# 06-STM32WL3-RX.net
KiCad netlist of a schematic drawn in Altium Designer
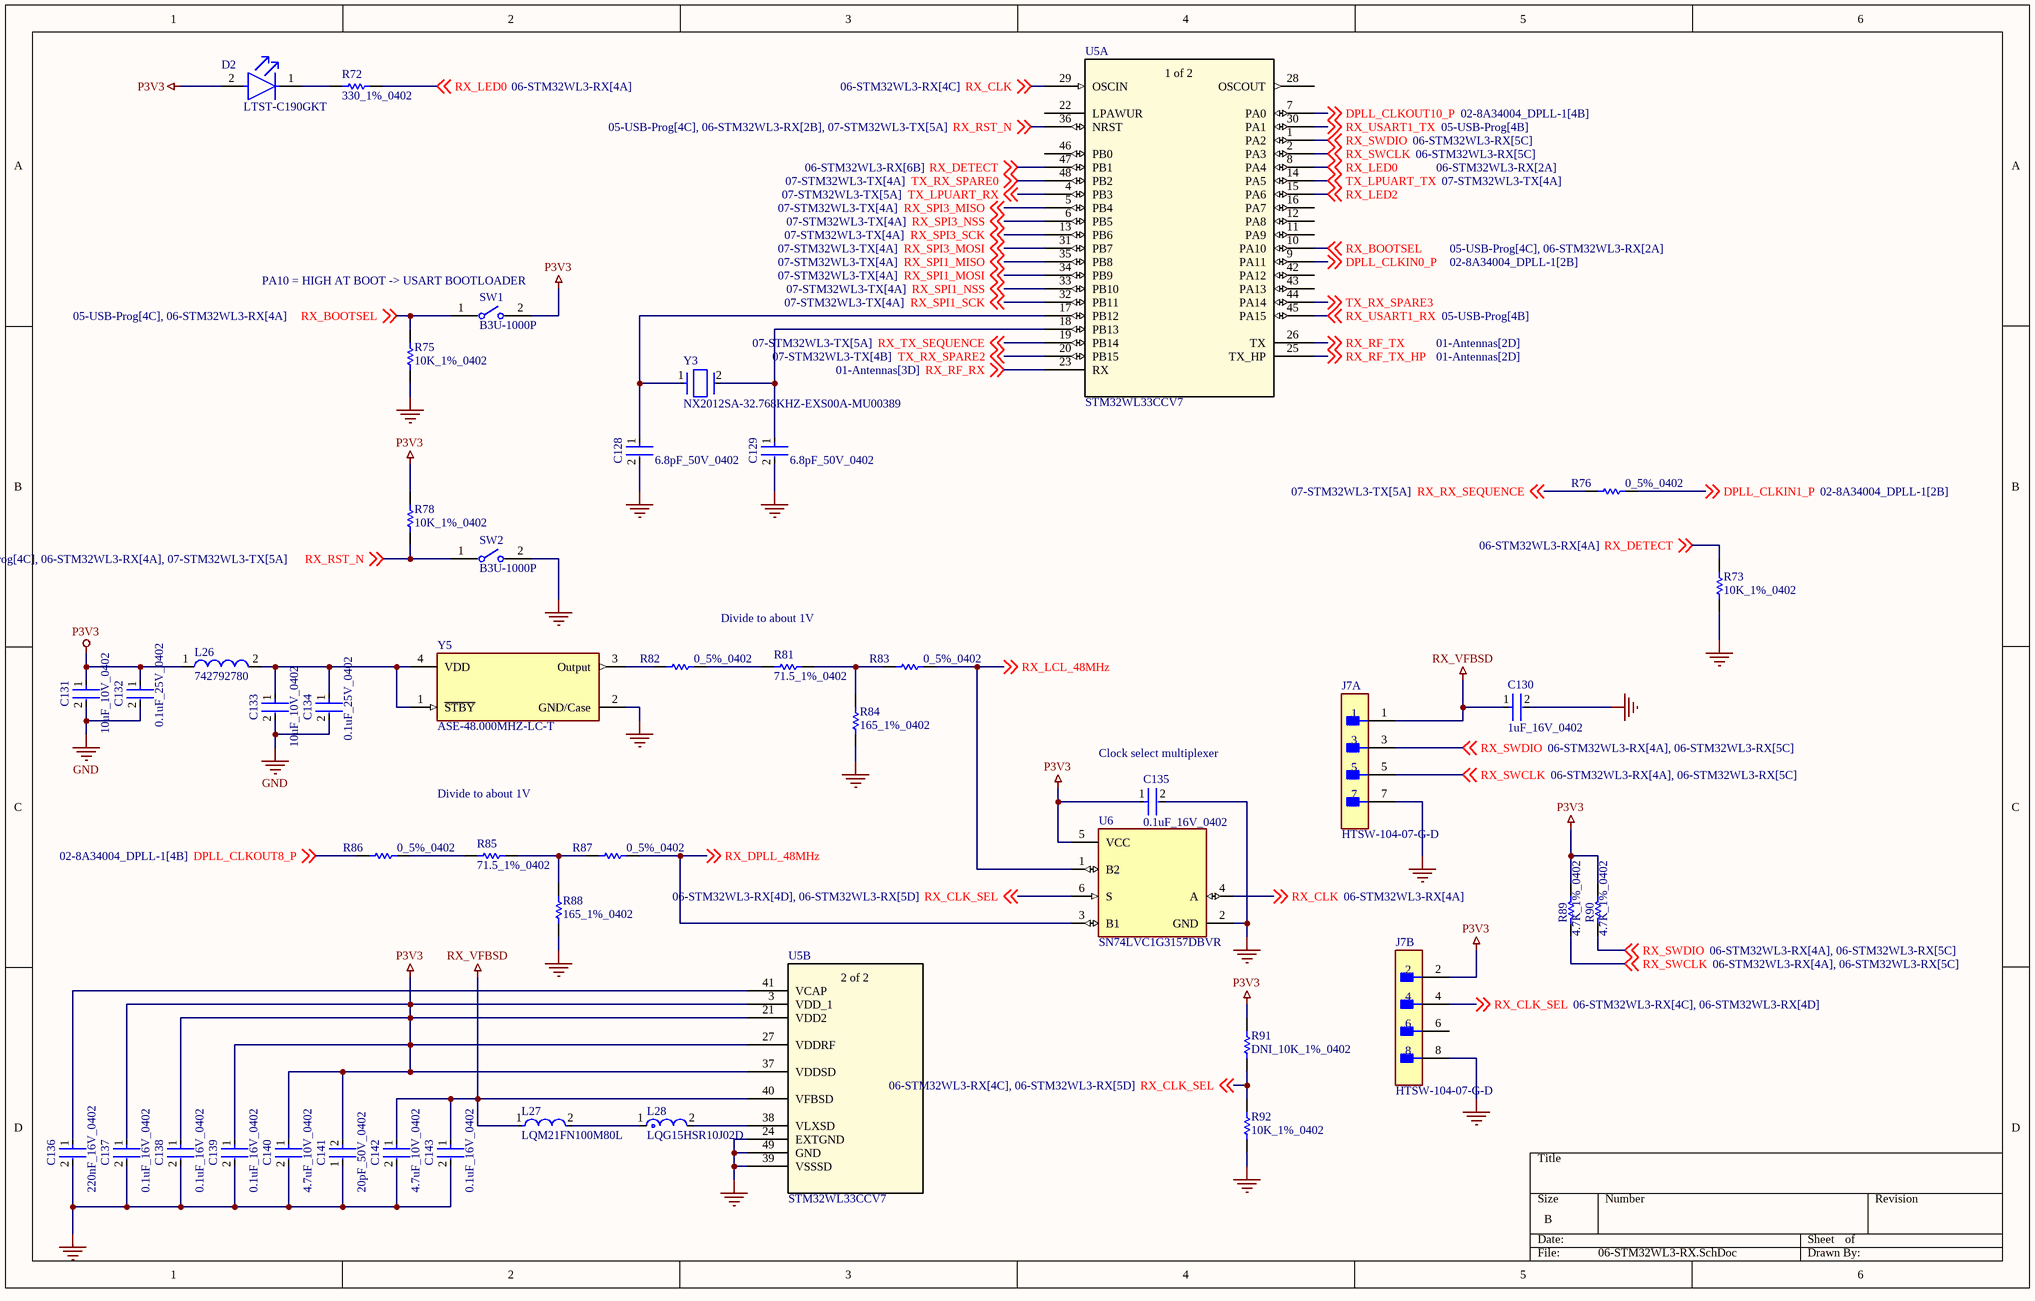
[diagram p0: 06-STM32WL3-RX.SchDoc]

(export (version "E")
  (design (tool "Eeschema 10.0.6"))
  (components
    (comp (ref "C128")
      (value "6.8pF_50V_0402")
      (footprint "FP-GJM155-0_05-IPC_A")
      (description "Multi-Layer Ceramic Capacitor 6.8pF C0G  ±0.25pF 0402 Paper T/R")
      (fields (field (name "VOLTAGE") "50V"))
      (libsource (lib "Altium Content Vault") (part "02cd4be3c70576c341d710602a673aa"))
    )
    (comp (ref "C129")
      (value "6.8pF_50V_0402")
      (footprint "FP-GJM155-0_05-IPC_A")
      (description "Multi-Layer Ceramic Capacitor 6.8pF C0G  ±0.25pF 0402 Paper T/R")
      (fields (field (name "VOLTAGE") "50V"))
      (libsource (lib "Altium Content Vault") (part "02cd4be3c70576c341d710602a673aa"))
    )
    (comp (ref "C130")
      (value "1uF_16V_0402")
      (footprint "FP-0402-L_1_0_0_05-W_0_5-IPC_A")
      (description "None")
      (fields (field (name "TOLERANCE") "10%"))
      (libsource (lib "Altium Content Vault") (part "b4654b650e69147ec39a6b967a45e02"))
    )
    (comp (ref "C131")
      (value "10uF_10V_0402")
      (footprint "FP-CL05A106MP5NUNC-MFG")
      (description "CAP CER 10UF 10V X5R 0402")
      (fields
        (field (name "OCTOPART") "https://octopart.com/cl05a106mp5nunc-samsung-22457395")
        (field (name "TOLERANCE") "20%")
      )
      (libsource (lib "Altium Content Vault") (part "b4654b650e69147ec39a6b967a45e02"))
    )
    (comp (ref "C132")
      (value "0.1uF_25V_0402")
      (footprint "FP-0402-L_1_0_1-W_0_5_0_1-IPC_C")
      (description "General Purpose Ceramic Capacitor, 0402, 100nF, 10%, X7R, 15%, 25V")
      (fields (field (name "VOLTAGE") "25V") (field (name "TOLERANCE") "10%"))
      (libsource (lib "Altium Content Vault") (part "b4654b650e69147ec39a6b967a45e02"))
    )
    (comp (ref "C133")
      (value "10uF_10V_0402")
      (footprint "FP-CL05A106MP5NUNC-MFG")
      (description "CAP CER 10UF 10V X5R 0402")
      (fields
        (field (name "OCTOPART") "https://octopart.com/cl05a106mp5nunc-samsung-22457395")
        (field (name "TOLERANCE") "20%")
      )
      (libsource (lib "Altium Content Vault") (part "b4654b650e69147ec39a6b967a45e02"))
    )
    (comp (ref "C134")
      (value "0.1uF_25V_0402")
      (footprint "FP-0402-L_1_0_1-W_0_5_0_1-IPC_C")
      (description "General Purpose Ceramic Capacitor, 0402, 100nF, 10%, X7R, 15%, 25V")
      (fields (field (name "VOLTAGE") "25V") (field (name "TOLERANCE") "10%"))
      (libsource (lib "Altium Content Vault") (part "b4654b650e69147ec39a6b967a45e02"))
    )
    (comp (ref "C135")
      (value "0.1uF_16V_0402")
      (footprint "FP-C0402-BB-MFG")
      (description "CAP CER 0.1UF 16V 5% X7R 0402")
      (fields
        (field (name "MANUFACTURER") "Kemet")
        (field (name "MANUFACTURER PART NUMBER") "C0402C104J4RACTU")
      )
      (libsource (lib "Altium Content Vault") (part "b4654b650e69147ec39a6b967a45e02"))
    )
    (comp (ref "C136")
      (value "220nF_16V_0402")
      (footprint "FP-GRM155-0_05-IPC_C")
      (description "Chip Multilayer Ceramic Capacitors for General Purpose, 0402, 0.22uF, X7R, 15%, 10%, 16V")
      (fields (field (name "VOLTAGE") "16V") (field (name "TOLERANCE") "10%"))
      (libsource (lib "Altium Content Vault") (part "02cd4be3c70576c341d710602a673aa"))
    )
    (comp (ref "C137")
      (value "0.1uF_16V_0402")
      (footprint "FP-C0402-BB-MFG")
      (description "CAP CER 0.1UF 16V 5% X7R 0402")
      (fields
        (field (name "MANUFACTURER") "Kemet")
        (field (name "MANUFACTURER PART NUMBER") "C0402C104J4RACTU")
      )
      (libsource (lib "Altium Content Vault") (part "b4654b650e69147ec39a6b967a45e02"))
    )
    (comp (ref "C138")
      (value "0.1uF_16V_0402")
      (footprint "FP-C0402-BB-MFG")
      (description "CAP CER 0.1UF 16V 5% X7R 0402")
      (fields
        (field (name "MANUFACTURER") "Kemet")
        (field (name "MANUFACTURER PART NUMBER") "C0402C104J4RACTU")
      )
      (libsource (lib "Altium Content Vault") (part "b4654b650e69147ec39a6b967a45e02"))
    )
    (comp (ref "C139")
      (value "0.1uF_16V_0402")
      (footprint "FP-C0402-BB-MFG")
      (description "CAP CER 0.1UF 16V 5% X7R 0402")
      (fields
        (field (name "MANUFACTURER") "Kemet")
        (field (name "MANUFACTURER PART NUMBER") "C0402C104J4RACTU")
      )
      (libsource (lib "Altium Content Vault") (part "b4654b650e69147ec39a6b967a45e02"))
    )
    (comp (ref "C140")
      (value "4.7uF_10V_0402")
      (footprint "FP-C1005-050-0_15-MFG")
      (description "CAP CER 4.7UF 10V X5R 0402")
      (fields (field (name "TOLERANCE") "10%"))
      (libsource (lib "Altium Content Vault") (part "b4654b650e69147ec39a6b967a45e02"))
    )
    (comp (ref "C141")
      (value "20pF_50V_0402")
      (footprint "FP-CBR04C-MFG")
      (description "CAP CER 20PF 50V C0G/NP0 0402")
      (fields
        (field (name "MANUFACTURER") "KEMET")
        (field (name "OCTOPART") "https://octopart.com/cbr04c200j5gac-kemet-20446742")
      )
      (libsource (lib "Altium Content Vault") (part "236180d848d6139a670b325ea6854c9"))
    )
    (comp (ref "C142")
      (value "4.7uF_10V_0402")
      (footprint "FP-C1005-050-0_15-MFG")
      (description "CAP CER 4.7UF 10V X5R 0402")
      (fields (field (name "TOLERANCE") "10%"))
      (libsource (lib "Altium Content Vault") (part "b4654b650e69147ec39a6b967a45e02"))
    )
    (comp (ref "C143")
      (value "0.1uF_16V_0402")
      (footprint "FP-C0402-BB-MFG")
      (description "CAP CER 0.1UF 16V 5% X7R 0402")
      (fields
        (field (name "MANUFACTURER") "Kemet")
        (field (name "MANUFACTURER PART NUMBER") "C0402C104J4RACTU")
      )
      (libsource (lib "Altium Content Vault") (part "b4654b650e69147ec39a6b967a45e02"))
    )
    (comp (ref "D2")
      (value "LTST-C190GKT")
      (footprint "FP-LTST-C190GKT-MFG")
      (description "LED GREEN CLEAR CHIP SMD")
      (fields (field (name "VOLTAGE") "2V"))
      (libsource (lib "Altium Content Vault") (part "8706943c75ba83719d021d2fdc84c58"))
    )
    (comp (ref "J7")
      (value "HTSW-104-07-G-D")
      (footprint "FP-HTSW-104-07-G-D-MFG")
      (description "CONN HEADER VERT 8POS 2.54MM")
      (fields
        (field (name "MANUFACTURER") "Samtec")
        (field (name "OCTOPART") "https://octopart.com/htsw-104-07-g-d-samtec-10613822")
      )
      (libsource (lib "Altium Content Vault") (part "811e954b9c034aa737de4d9295cbe7e"))
    )
    (comp (ref "L26")
      (value "742792780")
      (footprint "SMD-0402")
      (description "SMD EMI Suppression Ferrite Bead WE-CBF, Z = 220 Ohm")
      (libsource (lib "Altium Content Vault") (part "PAS-IND-INDUCTOR-2"))
    )
    (comp (ref "L27")
      (value "LQM21FN100M80L")
      (footprint "FP-LQM21DH_70-IPC_C")
      (description "Multilayer Type Inductor for Power Lines, 0805 (2012), 10μH, 20%, 0.39Ω, 100mA")
      (fields (field (name "TOLERANCE") "20%"))
      (libsource (lib "Altium Content Vault") (part "725321dda6339637d4d059423bc1c3c"))
    )
    (comp (ref "L28")
      (value "LQG15HSR10J02D")
      (footprint "FP-LQG15HH_02-IPC_A")
      (description "Multilayer type RF Inductor 100nH ±5% 1.25Ω 200mA 0402")
      (fields (field (name "TOLERANCE") "5%"))
      (libsource (lib "Altium Content Vault") (part "4cc4b267dca4c8e51f7102f422741d8"))
    )
    (comp (ref "R72")
      (value "330_1%_0402")
      (footprint "RESC1005X40X25NL10T10")
      (fields (field (name "MANUFACTURER") "Panasonic") (field (name "PART NUMBER") "ERA-2AED331X"))
      (libsource (lib "Altium Content Vault") (part "RES"))
    )
    (comp (ref "R73")
      (value "10K_1%_0402")
      (footprint "RESC1005X40X25NL10T10")
      (fields (field (name "MANUFACTURER") "Bourns") (field (name "PART NUMBER") "CR0402-FX-1002GLF"))
      (libsource (lib "Altium Content Vault") (part "RES"))
    )
    (comp (ref "R75")
      (value "10K_1%_0402")
      (footprint "RESC1005X40X25NL10T10")
      (fields (field (name "MANUFACTURER") "Bourns") (field (name "PART NUMBER") "CR0402-FX-1002GLF"))
      (libsource (lib "Altium Content Vault") (part "RES"))
    )
    (comp (ref "R76")
      (value "0_5%_0402")
      (footprint "RESC1005X40X25NL05T10")
      (fields (field (name "MANUFACTURER") "Panasonic") (field (name "PART NUMBER") "ERJ-U020R00X"))
      (libsource (lib "Altium Content Vault") (part "RES"))
    )
    (comp (ref "R78")
      (value "10K_1%_0402")
      (footprint "RESC1005X40X25NL10T10")
      (fields (field (name "MANUFACTURER") "Bourns") (field (name "PART NUMBER") "CR0402-FX-1002GLF"))
      (libsource (lib "Altium Content Vault") (part "RES"))
    )
    (comp (ref "R81")
      (value "71.5_1%_0402")
      (footprint "RESC1005X40X25NL05T05")
      (fields (field (name "MANUFACTURER") "Vishay Dale") (field (name "PART NUMBER") "CRCW040271R5FKED"))
      (libsource (lib "Altium Content Vault") (part "RES"))
    )
    (comp (ref "R82")
      (value "0_5%_0402")
      (footprint "RESC1005X40X25NL05T10")
      (fields (field (name "MANUFACTURER") "Panasonic") (field (name "PART NUMBER") "ERJ-U020R00X"))
      (libsource (lib "Altium Content Vault") (part "RES"))
    )
    (comp (ref "R83")
      (value "0_5%_0402")
      (footprint "RESC1005X40X25NL05T10")
      (fields (field (name "MANUFACTURER") "Panasonic") (field (name "PART NUMBER") "ERJ-U020R00X"))
      (libsource (lib "Altium Content Vault") (part "RES"))
    )
    (comp (ref "R84")
      (value "165_1%_0402")
      (footprint "RESC1005X40X25NL05T05")
      (fields (field (name "MANUFACTURER") "Vishay Dale") (field (name "PART NUMBER") "CRCW0402165RFKED"))
      (libsource (lib "Altium Content Vault") (part "RES"))
    )
    (comp (ref "R85")
      (value "71.5_1%_0402")
      (footprint "RESC1005X40X25NL05T05")
      (fields (field (name "MANUFACTURER") "Vishay Dale") (field (name "PART NUMBER") "CRCW040271R5FKED"))
      (libsource (lib "Altium Content Vault") (part "RES"))
    )
    (comp (ref "R86")
      (value "0_5%_0402")
      (footprint "RESC1005X40X25NL05T10")
      (fields (field (name "MANUFACTURER") "Panasonic") (field (name "PART NUMBER") "ERJ-U020R00X"))
      (libsource (lib "Altium Content Vault") (part "RES"))
    )
    (comp (ref "R87")
      (value "0_5%_0402")
      (footprint "RESC1005X40X25NL05T10")
      (fields (field (name "MANUFACTURER") "Panasonic") (field (name "PART NUMBER") "ERJ-U020R00X"))
      (libsource (lib "Altium Content Vault") (part "RES"))
    )
    (comp (ref "R88")
      (value "165_1%_0402")
      (footprint "RESC1005X40X25NL05T05")
      (fields (field (name "MANUFACTURER") "Vishay Dale") (field (name "PART NUMBER") "CRCW0402165RFKED"))
      (libsource (lib "Altium Content Vault") (part "RES"))
    )
    (comp (ref "R89")
      (value "4.7K_1%_0402")
      (footprint "RESC1005X40X25NL10T10")
      (fields (field (name "MANUFACTURER") "Bourns") (field (name "PART NUMBER") "CR0402-FX-4701GLF"))
      (libsource (lib "Altium Content Vault") (part "RES"))
    )
    (comp (ref "R90")
      (value "4.7K_1%_0402")
      (footprint "RESC1005X40X25NL10T10")
      (fields (field (name "MANUFACTURER") "Bourns") (field (name "PART NUMBER") "CR0402-FX-4701GLF"))
      (libsource (lib "Altium Content Vault") (part "RES"))
    )
    (comp (ref "R91")
      (value "DNI_10K_1%_0402")
      (footprint "RESC1005X40X25NL10T10")
      (fields (field (name "MANUFACTURER") "Bourns") (field (name "PART NUMBER") "CR0402-FX-1002GLF"))
      (libsource (lib "Altium Content Vault") (part "RES"))
    )
    (comp (ref "R92")
      (value "10K_1%_0402")
      (footprint "RESC1005X40X25NL10T10")
      (fields (field (name "MANUFACTURER") "Bourns") (field (name "PART NUMBER") "CR0402-FX-1002GLF"))
      (libsource (lib "Altium Content Vault") (part "RES"))
    )
    (comp (ref "SW1")
      (value "B3U-1000P")
      (footprint "FP-B3U-1000P-MFG")
      (description "SWITCH TACTILE SPST-NO 0.05A 12V")
      (libsource (lib "Altium Content Vault") (part "ae622034201233ca1abcedc05908f33"))
    )
    (comp (ref "SW2")
      (value "B3U-1000P")
      (footprint "FP-B3U-1000P-MFG")
      (description "SWITCH TACTILE SPST-NO 0.05A 12V")
      (libsource (lib "Altium Content Vault") (part "ae622034201233ca1abcedc05908f33"))
    )
    (comp (ref "U5")
      (value "STM32WL33CCV7")
      (footprint "UFQFPN-48_STM")
      (description "No Description Available")
      (libsource (lib "STM32WL33CCV7") (part "STM32WL33CCV7"))
    )
    (comp (ref "U6")
      (value "SN74LVC1G3157DBVR")
      (footprint "FP-DBV0006A-IPC_C")
      (description "IC SWITCH SPDT SOT23-6")
      (libsource (lib "Altium Content Vault") (part "14cfcf06f1431fbc89496e2a44d6624"))
    )
    (comp (ref "Y3")
      (value "NX2012SA-32.768KHZ-EXS00A-MU00389")
      (footprint "FP-NX2012SA-MFG")
      (description "CRYSTAL 32.768KHZ 7PF SMD")
      (fields
        (field (name "MANUFACTURER") "NDK America")
        (field (name "OCTOPART") "https://octopart.com/nx2012sa-32.768khz-exs00a-mu00389-ndk-92010294")
      )
      (libsource (lib "Altium Content Vault") (part "c23a69dc6c9e2f18f2079038eb95dd1"))
    )
    (comp (ref "Y5")
      (value "ASE-48.000MHZ-LC-T")
      (footprint "FP-ASE-MFG")
      (description "XTAL Oscillator 48MHz ±50ppm CMOS 3.3V 4-SMD 3.2mm x 2.5mm")
      (libsource (lib "Altium Content Vault") (part "61a724e6190563596ac712fef61ad37"))
    )
  )
  (nets
    (net (code "1") (name "DPLL_CLKIN0_P") (class "Default")
      (node (ref "U5") (pin "9") (pinfunction "PA11_9") (pintype "bidirectional"))
    )
    (net (code "2") (name "DPLL_CLKIN1_P") (class "Default")
      (node (ref "R76") (pin "2") (pinfunction "2_2") (pintype "passive"))
    )
    (net (code "3") (name "DPLL_CLKOUT8_P") (class "Default")
      (node (ref "R86") (pin "1") (pinfunction "1_1") (pintype "passive"))
    )
    (net (code "4") (name "DPLL_CLKOUT10_P") (class "Default")
      (node (ref "U5") (pin "7") (pinfunction "PA0_7") (pintype "bidirectional"))
    )
    (net (code "5") (name "GND") (class "Default")
      (node (ref "C128") (pin "2") (pinfunction "2_2") (pintype "passive"))
      (node (ref "C129") (pin "2") (pinfunction "2_2") (pintype "passive"))
      (node (ref "C130") (pin "2") (pinfunction "2_2") (pintype "passive"))
      (node (ref "C131") (pin "2") (pinfunction "2_2") (pintype "passive"))
      (node (ref "C132") (pin "2") (pinfunction "2_2") (pintype "passive"))
      (node (ref "C133") (pin "2") (pinfunction "2_2") (pintype "passive"))
      (node (ref "C134") (pin "2") (pinfunction "2_2") (pintype "passive"))
      (node (ref "C135") (pin "2") (pinfunction "2_2") (pintype "passive"))
      (node (ref "C136") (pin "2") (pinfunction "2_2") (pintype "passive"))
      (node (ref "C137") (pin "2") (pinfunction "2_2") (pintype "passive"))
      (node (ref "C138") (pin "2") (pinfunction "2_2") (pintype "passive"))
      (node (ref "C139") (pin "2") (pinfunction "2_2") (pintype "passive"))
      (node (ref "C140") (pin "2") (pinfunction "2_2") (pintype "passive"))
      (node (ref "C141") (pin "1") (pinfunction "1_1") (pintype "passive"))
      (node (ref "C142") (pin "2") (pinfunction "2_2") (pintype "passive"))
      (node (ref "C143") (pin "2") (pinfunction "2_2") (pintype "passive"))
      (node (ref "J7") (pin "7") (pinfunction "7_7") (pintype "passive"))
      (node (ref "J7") (pin "8") (pinfunction "8_8") (pintype "passive"))
      (node (ref "R73") (pin "2") (pinfunction "2_2") (pintype "passive"))
      (node (ref "R75") (pin "2") (pinfunction "2_2") (pintype "passive"))
      (node (ref "R84") (pin "1") (pinfunction "1_1") (pintype "passive"))
      (node (ref "R88") (pin "1") (pinfunction "1_1") (pintype "passive"))
      (node (ref "R92") (pin "2") (pinfunction "2_2") (pintype "passive"))
      (node (ref "SW2") (pin "2") (pinfunction "2_2") (pintype "passive"))
      (node (ref "U5") (pin "24") (pinfunction "EXTGND_24") (pintype "power_in"))
      (node (ref "U5") (pin "39") (pinfunction "VSSSD_39") (pintype "power_in"))
      (node (ref "U5") (pin "49") (pinfunction "GND_49") (pintype "power_in"))
      (node (ref "U6") (pin "2") (pinfunction "GND_2") (pintype "power_in"))
      (node (ref "Y5") (pin "2") (pinfunction "GND/Case_2") (pintype "power_in"))
    )
    (net (code "6") (name "Net-(D2-C)") (class "Default")
      (node (ref "D2") (pin "1") (pinfunction "C_1") (pintype "passive"))
      (node (ref "R72") (pin "2") (pinfunction "2_2") (pintype "passive"))
    )
    (net (code "7") (name "Net-(L27-Pad2)") (class "Default")
      (node (ref "L27") (pin "2") (pinfunction "2_2") (pintype "passive"))
      (node (ref "L28") (pin "1") (pinfunction "1_1") (pintype "passive"))
    )
    (net (code "8") (name "Net-(R81-Pad1)") (class "Default")
      (node (ref "R81") (pin "1") (pinfunction "1_1") (pintype "passive"))
      (node (ref "R82") (pin "2") (pinfunction "2_2") (pintype "passive"))
    )
    (net (code "9") (name "Net-(R81-Pad2)") (class "Default")
      (node (ref "R81") (pin "2") (pinfunction "2_2") (pintype "passive"))
      (node (ref "R83") (pin "1") (pinfunction "1_1") (pintype "passive"))
      (node (ref "R84") (pin "2") (pinfunction "2_2") (pintype "passive"))
    )
    (net (code "10") (name "Net-(R85-Pad1)") (class "Default")
      (node (ref "R85") (pin "1") (pinfunction "1_1") (pintype "passive"))
      (node (ref "R86") (pin "2") (pinfunction "2_2") (pintype "passive"))
    )
    (net (code "11") (name "Net-(R85-Pad2)") (class "Default")
      (node (ref "R85") (pin "2") (pinfunction "2_2") (pintype "passive"))
      (node (ref "R87") (pin "1") (pinfunction "1_1") (pintype "passive"))
      (node (ref "R88") (pin "2") (pinfunction "2_2") (pintype "passive"))
    )
    (net (code "12") (name "Net-(U5A-PB12)") (class "Default")
      (node (ref "C128") (pin "1") (pinfunction "1_1") (pintype "passive"))
      (node (ref "U5") (pin "17") (pinfunction "PB12_17") (pintype "bidirectional"))
      (node (ref "Y3") (pin "1") (pinfunction "1_1") (pintype "passive"))
    )
    (net (code "13") (name "Net-(U5A-PB13)") (class "Default")
      (node (ref "C129") (pin "1") (pinfunction "1_1") (pintype "passive"))
      (node (ref "U5") (pin "18") (pinfunction "PB13_18") (pintype "bidirectional"))
      (node (ref "Y3") (pin "2") (pinfunction "2_2") (pintype "passive"))
    )
    (net (code "14") (name "Net-(U5B-VCAP)") (class "Default")
      (node (ref "C136") (pin "1") (pinfunction "1_1") (pintype "passive"))
      (node (ref "U5") (pin "41") (pinfunction "VCAP_41") (pintype "power_in"))
    )
    (net (code "15") (name "Net-(U5B-VLXSD)") (class "Default")
      (node (ref "L28") (pin "2") (pinfunction "2_2") (pintype "passive"))
      (node (ref "U5") (pin "38") (pinfunction "VLXSD_38") (pintype "power_in"))
    )
    (net (code "16") (name "Net-(Y5-Output)") (class "Default")
      (node (ref "R82") (pin "1") (pinfunction "1_1") (pintype "passive"))
      (node (ref "Y5") (pin "3") (pinfunction "Output_3") (pintype "output"))
    )
    (net (code "17") (name "Net-(Y5-VDD)") (class "Default")
      (node (ref "C133") (pin "1") (pinfunction "1_1") (pintype "passive"))
      (node (ref "C134") (pin "1") (pinfunction "1_1") (pintype "passive"))
      (node (ref "L26") (pin "2") (pinfunction "2_2") (pintype "passive"))
      (node (ref "Y5") (pin "1") (pinfunction "~{STBY}_1") (pintype "input"))
      (node (ref "Y5") (pin "4") (pinfunction "VDD_4") (pintype "power_in"))
    )
    (net (code "18") (name "P3V3") (class "Default")
      (node (ref "C131") (pin "1") (pinfunction "1_1") (pintype "passive"))
      (node (ref "C132") (pin "1") (pinfunction "1_1") (pintype "passive"))
      (node (ref "C135") (pin "1") (pinfunction "1_1") (pintype "passive"))
      (node (ref "C137") (pin "1") (pinfunction "1_1") (pintype "passive"))
      (node (ref "C138") (pin "1") (pinfunction "1_1") (pintype "passive"))
      (node (ref "C139") (pin "1") (pinfunction "1_1") (pintype "passive"))
      (node (ref "C140") (pin "1") (pinfunction "1_1") (pintype "passive"))
      (node (ref "C141") (pin "2") (pinfunction "2_2") (pintype "passive"))
      (node (ref "D2") (pin "2") (pinfunction "A_2") (pintype "passive"))
      (node (ref "J7") (pin "2") (pinfunction "2_2") (pintype "passive"))
      (node (ref "L26") (pin "1") (pinfunction "1_1") (pintype "passive"))
      (node (ref "R78") (pin "1") (pinfunction "1_1") (pintype "passive"))
      (node (ref "R89") (pin "2") (pinfunction "2_2") (pintype "passive"))
      (node (ref "R90") (pin "2") (pinfunction "2_2") (pintype "passive"))
      (node (ref "R91") (pin "1") (pinfunction "1_1") (pintype "passive"))
      (node (ref "SW1") (pin "2") (pinfunction "2_2") (pintype "passive"))
      (node (ref "U5") (pin "21") (pinfunction "VDD2_21") (pintype "power_in"))
      (node (ref "U5") (pin "27") (pinfunction "VDDRF_27") (pintype "power_in"))
      (node (ref "U5") (pin "3") (pinfunction "VDD_1_3") (pintype "power_in"))
      (node (ref "U5") (pin "37") (pinfunction "VDDSD_37") (pintype "power_in"))
      (node (ref "U6") (pin "5") (pinfunction "VCC_5") (pintype "power_in"))
    )
    (net (code "19") (name "RX_BOOTSEL") (class "Default")
      (node (ref "R75") (pin "1") (pinfunction "1_1") (pintype "passive"))
      (node (ref "SW1") (pin "1") (pinfunction "1_1") (pintype "passive"))
      (node (ref "U5") (pin "10") (pinfunction "PA10_10") (pintype "bidirectional"))
    )
    (net (code "20") (name "RX_CLK") (class "Default")
      (node (ref "U5") (pin "29") (pinfunction "OSCIN_29") (pintype "input"))
      (node (ref "U6") (pin "4") (pinfunction "A_4") (pintype "bidirectional"))
    )
    (net (code "21") (name "RX_CLK_SEL") (class "Default")
      (node (ref "J7") (pin "4") (pinfunction "4_4") (pintype "passive"))
      (node (ref "R91") (pin "2") (pinfunction "2_2") (pintype "passive"))
      (node (ref "R92") (pin "1") (pinfunction "1_1") (pintype "passive"))
      (node (ref "U6") (pin "6") (pinfunction "S_6") (pintype "input"))
    )
    (net (code "22") (name "RX_DETECT") (class "Default")
      (node (ref "R73") (pin "1") (pinfunction "1_1") (pintype "passive"))
      (node (ref "U5") (pin "47") (pinfunction "PB1_47") (pintype "bidirectional"))
    )
    (net (code "23") (name "RX_DPLL_48MHz") (class "Default")
      (node (ref "R87") (pin "2") (pinfunction "2_2") (pintype "passive"))
      (node (ref "U6") (pin "3") (pinfunction "B1_3") (pintype "bidirectional"))
    )
    (net (code "24") (name "RX_LCL_48MHz") (class "Default")
      (node (ref "R83") (pin "2") (pinfunction "2_2") (pintype "passive"))
      (node (ref "U6") (pin "1") (pinfunction "B2_1") (pintype "bidirectional"))
    )
    (net (code "25") (name "RX_LED0") (class "Default")
      (node (ref "R72") (pin "1") (pinfunction "1_1") (pintype "passive"))
      (node (ref "U5") (pin "8") (pinfunction "PA4_8") (pintype "bidirectional"))
    )
    (net (code "26") (name "RX_LED2") (class "Default")
      (node (ref "U5") (pin "15") (pinfunction "PA6_15") (pintype "bidirectional"))
    )
    (net (code "27") (name "RX_RF_RX") (class "Default")
      (node (ref "U5") (pin "23") (pinfunction "RX_23") (pintype "passive"))
    )
    (net (code "28") (name "RX_RF_TX") (class "Default")
      (node (ref "U5") (pin "26") (pinfunction "TX_26") (pintype "passive"))
    )
    (net (code "29") (name "RX_RF_TX_HP") (class "Default")
      (node (ref "U5") (pin "25") (pinfunction "TX_HP_25") (pintype "passive"))
    )
    (net (code "30") (name "RX_RST_N") (class "Default")
      (node (ref "R78") (pin "2") (pinfunction "2_2") (pintype "passive"))
      (node (ref "SW2") (pin "1") (pinfunction "1_1") (pintype "passive"))
      (node (ref "U5") (pin "36") (pinfunction "NRST_36") (pintype "bidirectional"))
    )
    (net (code "31") (name "RX_RX_SEQUENCE") (class "Default")
      (node (ref "R76") (pin "1") (pinfunction "1_1") (pintype "passive"))
    )
    (net (code "32") (name "RX_SPI1_MISO") (class "Default")
      (node (ref "U5") (pin "35") (pinfunction "PB8_35") (pintype "bidirectional"))
    )
    (net (code "33") (name "RX_SPI1_MOSI") (class "Default")
      (node (ref "U5") (pin "34") (pinfunction "PB9_34") (pintype "bidirectional"))
    )
    (net (code "34") (name "RX_SPI1_NSS") (class "Default")
      (node (ref "U5") (pin "33") (pinfunction "PB10_33") (pintype "bidirectional"))
    )
    (net (code "35") (name "RX_SPI1_SCK") (class "Default")
      (node (ref "U5") (pin "32") (pinfunction "PB11_32") (pintype "bidirectional"))
    )
    (net (code "36") (name "RX_SPI3_MISO") (class "Default")
      (node (ref "U5") (pin "5") (pinfunction "PB4_5") (pintype "bidirectional"))
    )
    (net (code "37") (name "RX_SPI3_MOSI") (class "Default")
      (node (ref "U5") (pin "31") (pinfunction "PB7_31") (pintype "bidirectional"))
    )
    (net (code "38") (name "RX_SPI3_NSS") (class "Default")
      (node (ref "U5") (pin "6") (pinfunction "PB5_6") (pintype "bidirectional"))
    )
    (net (code "39") (name "RX_SPI3_SCK") (class "Default")
      (node (ref "U5") (pin "13") (pinfunction "PB6_13") (pintype "bidirectional"))
    )
    (net (code "40") (name "RX_SWCLK") (class "Default")
      (node (ref "J7") (pin "5") (pinfunction "5_5") (pintype "passive"))
      (node (ref "R89") (pin "1") (pinfunction "1_1") (pintype "passive"))
      (node (ref "U5") (pin "2") (pinfunction "PA3_2") (pintype "bidirectional"))
    )
    (net (code "41") (name "RX_SWDIO") (class "Default")
      (node (ref "J7") (pin "3") (pinfunction "3_3") (pintype "passive"))
      (node (ref "R90") (pin "1") (pinfunction "1_1") (pintype "passive"))
      (node (ref "U5") (pin "1") (pinfunction "PA2_1") (pintype "bidirectional"))
    )
    (net (code "42") (name "RX_TX_SEQUENCE") (class "Default")
      (node (ref "U5") (pin "19") (pinfunction "PB14_19") (pintype "bidirectional"))
    )
    (net (code "43") (name "RX_USART1_RX") (class "Default")
      (node (ref "U5") (pin "45") (pinfunction "PA15_45") (pintype "bidirectional"))
    )
    (net (code "44") (name "RX_USART1_TX") (class "Default")
      (node (ref "U5") (pin "30") (pinfunction "PA1_30") (pintype "bidirectional"))
    )
    (net (code "45") (name "RX_VFBSD") (class "Default")
      (node (ref "C130") (pin "1") (pinfunction "1_1") (pintype "passive"))
      (node (ref "C142") (pin "1") (pinfunction "1_1") (pintype "passive"))
      (node (ref "C143") (pin "1") (pinfunction "1_1") (pintype "passive"))
      (node (ref "J7") (pin "1") (pinfunction "1_1") (pintype "passive"))
      (node (ref "L27") (pin "1") (pinfunction "1_1") (pintype "passive"))
      (node (ref "U5") (pin "40") (pinfunction "VFBSD_40") (pintype "power_in"))
    )
    (net (code "46") (name "TX_LPUART_RX") (class "Default")
      (node (ref "U5") (pin "4") (pinfunction "PB3_4") (pintype "bidirectional"))
    )
    (net (code "47") (name "TX_LPUART_TX") (class "Default")
      (node (ref "U5") (pin "14") (pinfunction "PA5_14") (pintype "bidirectional"))
    )
    (net (code "48") (name "TX_RX_SPARE0") (class "Default")
      (node (ref "U5") (pin "48") (pinfunction "PB2_48") (pintype "bidirectional"))
    )
    (net (code "49") (name "TX_RX_SPARE2") (class "Default")
      (node (ref "U5") (pin "20") (pinfunction "PB15_20") (pintype "bidirectional"))
    )
    (net (code "50") (name "TX_RX_SPARE3") (class "Default")
      (node (ref "U5") (pin "44") (pinfunction "PA14_44") (pintype "bidirectional"))
    )
    (net (code "51") (name "unconnected-(J7-Pad6)") (class "Default")
      (node (ref "J7") (pin "6") (pinfunction "6_6") (pintype "passive"))
    )
    (net (code "52") (name "unconnected-(U5A-LPAWUR-Pad22)") (class "Default")
      (node (ref "U5") (pin "22") (pinfunction "LPAWUR_22") (pintype "passive"))
    )
    (net (code "53") (name "unconnected-(U5A-OSCOUT-Pad28)") (class "Default")
      (node (ref "U5") (pin "28") (pinfunction "OSCOUT_28") (pintype "output"))
    )
    (net (code "54") (name "unconnected-(U5A-PA7-Pad16)") (class "Default")
      (node (ref "U5") (pin "16") (pinfunction "PA7_16") (pintype "bidirectional"))
    )
    (net (code "55") (name "unconnected-(U5A-PA8-Pad12)") (class "Default")
      (node (ref "U5") (pin "12") (pinfunction "PA8_12") (pintype "bidirectional"))
    )
    (net (code "56") (name "unconnected-(U5A-PA9-Pad11)") (class "Default")
      (node (ref "U5") (pin "11") (pinfunction "PA9_11") (pintype "bidirectional"))
    )
    (net (code "57") (name "unconnected-(U5A-PA12-Pad42)") (class "Default")
      (node (ref "U5") (pin "42") (pinfunction "PA12_42") (pintype "bidirectional"))
    )
    (net (code "58") (name "unconnected-(U5A-PA13-Pad43)") (class "Default")
      (node (ref "U5") (pin "43") (pinfunction "PA13_43") (pintype "bidirectional"))
    )
    (net (code "59") (name "unconnected-(U5A-PB0-Pad46)") (class "Default")
      (node (ref "U5") (pin "46") (pinfunction "PB0_46") (pintype "bidirectional"))
    )
  )
)
